# USB_pinout.net
KiCad netlist of a schematic drawn in EAGLE
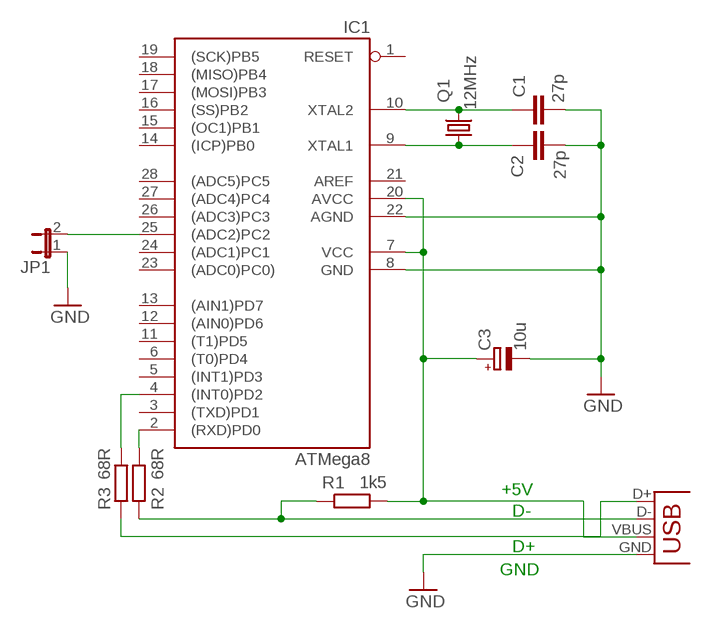
[diagram p0: schematic, sheet 2]

(export (version "E")
  (design (tool "Eeschema 10.0.6"))
  (components
    (comp (ref "C1")
      (value "27p")
      (footprint "eagle-import:C025-024X044")
      (libsource (lib "eagle-import") (part "C-EU025-024X044"))
    )
    (comp (ref "C2")
      (value "27p")
      (footprint "eagle-import:C025-024X044")
      (libsource (lib "eagle-import") (part "C-EU025-024X044"))
    )
    (comp (ref "C3")
      (value "10u")
      (footprint "eagle-import:E2,5-5")
      (libsource (lib "eagle-import") (part "CPOL-EUE2.5-5"))
    )
    (comp (ref "IC1")
      (value "ATMega8")
      (footprint "eagle-import:DIL28-3")
      (libsource (lib "eagle-import") (part "AT90S4433P"))
    )
    (comp (ref "JP1")
      (value "JP1E")
      (footprint "eagle-import:JP1")
      (libsource (lib "eagle-import") (part "JP1E"))
    )
    (comp (ref "Q1")
      (value "12MHz")
      (footprint "eagle-import:HC49_S")
      (libsource (lib "eagle-import") (part "CRYTALHC49S"))
    )
    (comp (ref "R1")
      (value "1k5")
      (footprint "eagle-import:0207_7")
      (libsource (lib "eagle-import") (part "R-EU_0207/7"))
    )
    (comp (ref "R2")
      (value "68R")
      (footprint "eagle-import:0207_7")
      (libsource (lib "eagle-import") (part "R-EU_0207/7"))
    )
    (comp (ref "R3")
      (value "68R")
      (footprint "eagle-import:0207_7")
      (libsource (lib "eagle-import") (part "R-EU_0207/7"))
    )
    (comp (ref "X3")
      (value "USB-B-H")
      (footprint "eagle-import:USB-B-H")
      (libsource (lib "eagle-import") (part "USB-B-H"))
    )
  )
  (nets
    (net (code "1") (name "AREF") (class "Default")
      (node (ref "IC1") (pin "21") (pinfunction "AREF_21") (pintype "power_in"))
    )
    (net (code "2") (name "GND") (class "Default")
      (node (ref "C1") (pin "2") (pinfunction "2_2") (pintype "passive"))
      (node (ref "C2") (pin "2") (pinfunction "2_2") (pintype "passive"))
      (node (ref "C3") (pin "-") (pinfunction "-_-") (pintype "passive"))
      (node (ref "IC1") (pin "22") (pinfunction "AGND_22") (pintype "power_in"))
      (node (ref "IC1") (pin "8") (pinfunction "GND_8") (pintype "power_in"))
      (node (ref "JP1") (pin "1") (pinfunction "1_1") (pintype "passive"))
      (node (ref "X3") (pin "GND") (pinfunction "GND_GND") (pintype "bidirectional"))
    )
    (net (code "3") (name "Net-(IC1-(ADC2)PC2)") (class "Default")
      (node (ref "IC1") (pin "25") (pinfunction "(ADC2)PC2_25") (pintype "bidirectional"))
      (node (ref "JP1") (pin "2") (pinfunction "2_2") (pintype "passive"))
    )
    (net (code "4") (name "Net-(IC1-(INT0)PD2)") (class "Default")
      (node (ref "IC1") (pin "4") (pinfunction "(INT0)PD2_4") (pintype "bidirectional"))
      (node (ref "R3") (pin "2") (pinfunction "2_2") (pintype "passive"))
    )
    (net (code "5") (name "Net-(IC1-(RXD)PD0)") (class "Default")
      (node (ref "IC1") (pin "2") (pinfunction "(RXD)PD0_2") (pintype "bidirectional"))
      (node (ref "R2") (pin "2") (pinfunction "2_2") (pintype "passive"))
    )
    (net (code "6") (name "Net-(IC1-AVCC)") (class "Default")
      (node (ref "C3") (pin "+") (pinfunction "+_+") (pintype "passive"))
      (node (ref "IC1") (pin "20") (pinfunction "AVCC_20") (pintype "power_in"))
      (node (ref "IC1") (pin "7") (pinfunction "VCC_7") (pintype "power_in"))
      (node (ref "R1") (pin "2") (pinfunction "2_2") (pintype "passive"))
      (node (ref "X3") (pin "VBUS") (pinfunction "VBUS_VBUS") (pintype "bidirectional"))
    )
    (net (code "7") (name "Net-(IC1-XTAL1)") (class "Default")
      (node (ref "C2") (pin "1") (pinfunction "1_1") (pintype "passive"))
      (node (ref "IC1") (pin "9") (pinfunction "XTAL1_9") (pintype "bidirectional"))
      (node (ref "Q1") (pin "1") (pinfunction "1_1") (pintype "passive"))
    )
    (net (code "8") (name "Net-(IC1-XTAL2)") (class "Default")
      (node (ref "C1") (pin "1") (pinfunction "1_1") (pintype "passive"))
      (node (ref "IC1") (pin "10") (pinfunction "XTAL2_10") (pintype "bidirectional"))
      (node (ref "Q1") (pin "2") (pinfunction "2_2") (pintype "passive"))
    )
    (net (code "9") (name "Net-(R1-Pad1)") (class "Default")
      (node (ref "R1") (pin "1") (pinfunction "1_1") (pintype "passive"))
      (node (ref "R2") (pin "1") (pinfunction "1_1") (pintype "passive"))
      (node (ref "X3") (pin "D-") (pinfunction "D-_D-") (pintype "bidirectional"))
    )
    (net (code "10") (name "Net-(R3-Pad1)") (class "Default")
      (node (ref "R3") (pin "1") (pinfunction "1_1") (pintype "passive"))
      (node (ref "X3") (pin "D+") (pinfunction "D+_D+") (pintype "bidirectional"))
    )
    (net (code "11") (name "unconnected-(IC1-(ADC0)PC0)-Pad23)") (class "Default")
      (node (ref "IC1") (pin "23") (pinfunction "(ADC0)PC0)_23") (pintype "bidirectional"))
    )
    (net (code "12") (name "unconnected-(IC1-(ADC1)PC1-Pad24)") (class "Default")
      (node (ref "IC1") (pin "24") (pinfunction "(ADC1)PC1_24") (pintype "bidirectional"))
    )
    (net (code "13") (name "unconnected-(IC1-(ADC3)PC3-Pad26)") (class "Default")
      (node (ref "IC1") (pin "26") (pinfunction "(ADC3)PC3_26") (pintype "bidirectional"))
    )
    (net (code "14") (name "unconnected-(IC1-(ADC4)PC4-Pad27)") (class "Default")
      (node (ref "IC1") (pin "27") (pinfunction "(ADC4)PC4_27") (pintype "bidirectional"))
    )
    (net (code "15") (name "unconnected-(IC1-(ADC5)PC5-Pad28)") (class "Default")
      (node (ref "IC1") (pin "28") (pinfunction "(ADC5)PC5_28") (pintype "bidirectional"))
    )
    (net (code "16") (name "unconnected-(IC1-(AIN0)PD6-Pad12)") (class "Default")
      (node (ref "IC1") (pin "12") (pinfunction "(AIN0)PD6_12") (pintype "bidirectional"))
    )
    (net (code "17") (name "unconnected-(IC1-(AIN1)PD7-Pad13)") (class "Default")
      (node (ref "IC1") (pin "13") (pinfunction "(AIN1)PD7_13") (pintype "bidirectional"))
    )
    (net (code "18") (name "unconnected-(IC1-(ICP)PB0-Pad14)") (class "Default")
      (node (ref "IC1") (pin "14") (pinfunction "(ICP)PB0_14") (pintype "bidirectional"))
    )
    (net (code "19") (name "unconnected-(IC1-(INT1)PD3-Pad5)") (class "Default")
      (node (ref "IC1") (pin "5") (pinfunction "(INT1)PD3_5") (pintype "bidirectional"))
    )
    (net (code "20") (name "unconnected-(IC1-(MISO)PB4-Pad18)") (class "Default")
      (node (ref "IC1") (pin "18") (pinfunction "(MISO)PB4_18") (pintype "bidirectional"))
    )
    (net (code "21") (name "unconnected-(IC1-(MOSI)PB3-Pad17)") (class "Default")
      (node (ref "IC1") (pin "17") (pinfunction "(MOSI)PB3_17") (pintype "bidirectional"))
    )
    (net (code "22") (name "unconnected-(IC1-(OC1)PB1-Pad15)") (class "Default")
      (node (ref "IC1") (pin "15") (pinfunction "(OC1)PB1_15") (pintype "bidirectional"))
    )
    (net (code "23") (name "unconnected-(IC1-(SCK)PB5-Pad19)") (class "Default")
      (node (ref "IC1") (pin "19") (pinfunction "(SCK)PB5_19") (pintype "bidirectional"))
    )
    (net (code "24") (name "unconnected-(IC1-(SS)PB2-Pad16)") (class "Default")
      (node (ref "IC1") (pin "16") (pinfunction "(SS)PB2_16") (pintype "bidirectional"))
    )
    (net (code "25") (name "unconnected-(IC1-(T0)PD4-Pad6)") (class "Default")
      (node (ref "IC1") (pin "6") (pinfunction "(T0)PD4_6") (pintype "bidirectional"))
    )
    (net (code "26") (name "unconnected-(IC1-(T1)PD5-Pad11)") (class "Default")
      (node (ref "IC1") (pin "11") (pinfunction "(T1)PD5_11") (pintype "bidirectional"))
    )
    (net (code "27") (name "unconnected-(IC1-(TXD)PD1-Pad3)") (class "Default")
      (node (ref "IC1") (pin "3") (pinfunction "(TXD)PD1_3") (pintype "bidirectional"))
    )
    (net (code "28") (name "unconnected-(IC1-RESET-Pad1)") (class "Default")
      (node (ref "IC1") (pin "1") (pinfunction "RESET_1") (pintype "input"))
    )
  )
)
